# interfaceBoard.net
KiCad netlist of a schematic drawn in EAGLE
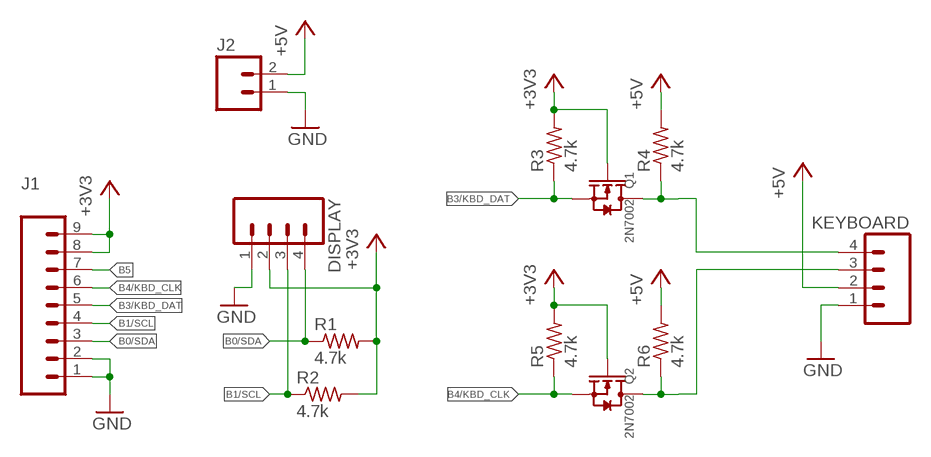
[diagram p0: schematic, sheet 1]

(export (version "E")
  (design (tool "Eeschema 10.0.6"))
  (components
    (comp (ref "DISPLAY")
      (value "M04LOCK_LONGPADS")
      (footprint "eagle-import:1X04_LOCK_LONGPADS")
      (libsource (lib "eagle-import") (part "M04LOCK_LONGPADS"))
    )
    (comp (ref "J1")
      (value "M09LOCK-LONGPADS")
      (footprint "eagle-import:1X09_LOCK_LONGPADS")
      (libsource (lib "eagle-import") (part "M09LOCK-LONGPADS"))
    )
    (comp (ref "J2")
      (value "M02PTH3")
      (footprint "eagle-import:1X02_LONGPADS")
      (libsource (lib "eagle-import") (part "M02PTH3"))
    )
    (comp (ref "KEYBOARD")
      (value "M04LOCK_LONGPADS")
      (footprint "eagle-import:1X04_LOCK_LONGPADS")
      (libsource (lib "eagle-import") (part "M04LOCK_LONGPADS"))
    )
    (comp (ref "Q1")
      (value "2N7002")
      (footprint "eagle-import:SOT-23")
      (fields (field (name "MPN") "2N7002,215"))
      (libsource (lib "eagle-import") (part "SMD-MOSFET-N-CH-60V-300MA-LOGIC-LEVEL-FET-2N7002(SOT-23)"))
    )
    (comp (ref "Q2")
      (value "2N7002")
      (footprint "eagle-import:SOT-23")
      (fields (field (name "MPN") "2N7002,215"))
      (libsource (lib "eagle-import") (part "SMD-MOSFET-N-CH-60V-300MA-LOGIC-LEVEL-FET-2N7002(SOT-23)"))
    )
    (comp (ref "R1")
      (value "4.7k")
      (footprint "eagle-import:R0805")
      (libsource (lib "eagle-import") (part "R-US_R0805"))
    )
    (comp (ref "R2")
      (value "4.7k")
      (footprint "eagle-import:R0805")
      (libsource (lib "eagle-import") (part "R-US_R0805"))
    )
    (comp (ref "R3")
      (value "4.7k")
      (footprint "eagle-import:R0805")
      (libsource (lib "eagle-import") (part "R-US_R0805"))
    )
    (comp (ref "R4")
      (value "4.7k")
      (footprint "eagle-import:R0805")
      (libsource (lib "eagle-import") (part "R-US_R0805"))
    )
    (comp (ref "R5")
      (value "4.7k")
      (footprint "eagle-import:R0805")
      (libsource (lib "eagle-import") (part "R-US_R0805"))
    )
    (comp (ref "R6")
      (value "4.7k")
      (footprint "eagle-import:R0805")
      (libsource (lib "eagle-import") (part "R-US_R0805"))
    )
  )
  (nets
    (net (code "1") (name "+3V3") (class "Default")
      (node (ref "DISPLAY") (pin "2") (pinfunction "2_2") (pintype "passive"))
      (node (ref "J1") (pin "8") (pinfunction "8_8") (pintype "passive"))
      (node (ref "J1") (pin "9") (pinfunction "9_9") (pintype "passive"))
      (node (ref "Q1") (pin "1") (pinfunction "G_1") (pintype "passive"))
      (node (ref "Q2") (pin "1") (pinfunction "G_1") (pintype "passive"))
      (node (ref "R1") (pin "2") (pinfunction "2_2") (pintype "passive"))
      (node (ref "R2") (pin "2") (pinfunction "2_2") (pintype "passive"))
      (node (ref "R3") (pin "2") (pinfunction "2_2") (pintype "passive"))
      (node (ref "R5") (pin "2") (pinfunction "2_2") (pintype "passive"))
    )
    (net (code "2") (name "+5V") (class "Default")
      (node (ref "J2") (pin "2") (pinfunction "2_2") (pintype "passive"))
      (node (ref "KEYBOARD") (pin "2") (pinfunction "2_2") (pintype "passive"))
      (node (ref "R4") (pin "2") (pinfunction "2_2") (pintype "passive"))
      (node (ref "R6") (pin "2") (pinfunction "2_2") (pintype "passive"))
    )
    (net (code "3") (name "B0{slash}SDA") (class "Default")
      (node (ref "DISPLAY") (pin "4") (pinfunction "4_4") (pintype "passive"))
      (node (ref "J1") (pin "3") (pinfunction "3_3") (pintype "passive"))
      (node (ref "R1") (pin "1") (pinfunction "1_1") (pintype "passive"))
    )
    (net (code "4") (name "B1{slash}SCL") (class "Default")
      (node (ref "DISPLAY") (pin "3") (pinfunction "3_3") (pintype "passive"))
      (node (ref "J1") (pin "4") (pinfunction "4_4") (pintype "passive"))
      (node (ref "R2") (pin "1") (pinfunction "1_1") (pintype "passive"))
    )
    (net (code "5") (name "B3{slash}KBD_DAT") (class "Default")
      (node (ref "J1") (pin "5") (pinfunction "5_5") (pintype "passive"))
      (node (ref "Q1") (pin "2") (pinfunction "S_2") (pintype "passive"))
      (node (ref "R3") (pin "1") (pinfunction "1_1") (pintype "passive"))
    )
    (net (code "6") (name "B4{slash}KBD_CLK") (class "Default")
      (node (ref "J1") (pin "6") (pinfunction "6_6") (pintype "passive"))
      (node (ref "Q2") (pin "2") (pinfunction "S_2") (pintype "passive"))
      (node (ref "R5") (pin "1") (pinfunction "1_1") (pintype "passive"))
    )
    (net (code "7") (name "B5") (class "Default")
      (node (ref "J1") (pin "7") (pinfunction "7_7") (pintype "passive"))
    )
    (net (code "8") (name "GND") (class "Default")
      (node (ref "DISPLAY") (pin "1") (pinfunction "1_1") (pintype "passive"))
      (node (ref "J1") (pin "1") (pinfunction "1_1") (pintype "passive"))
      (node (ref "J1") (pin "2") (pinfunction "2_2") (pintype "passive"))
      (node (ref "J2") (pin "1") (pinfunction "1_1") (pintype "passive"))
      (node (ref "KEYBOARD") (pin "1") (pinfunction "1_1") (pintype "passive"))
    )
    (net (code "9") (name "Net-(Q1-D)") (class "Default")
      (node (ref "KEYBOARD") (pin "4") (pinfunction "4_4") (pintype "passive"))
      (node (ref "Q1") (pin "3") (pinfunction "D_3") (pintype "passive"))
      (node (ref "R4") (pin "1") (pinfunction "1_1") (pintype "passive"))
    )
    (net (code "10") (name "Net-(Q2-D)") (class "Default")
      (node (ref "KEYBOARD") (pin "3") (pinfunction "3_3") (pintype "passive"))
      (node (ref "Q2") (pin "3") (pinfunction "D_3") (pintype "passive"))
      (node (ref "R6") (pin "1") (pinfunction "1_1") (pintype "passive"))
    )
  )
)
